# Domino_Pi.net
KiCad netlist of a schematic drawn in EAGLE
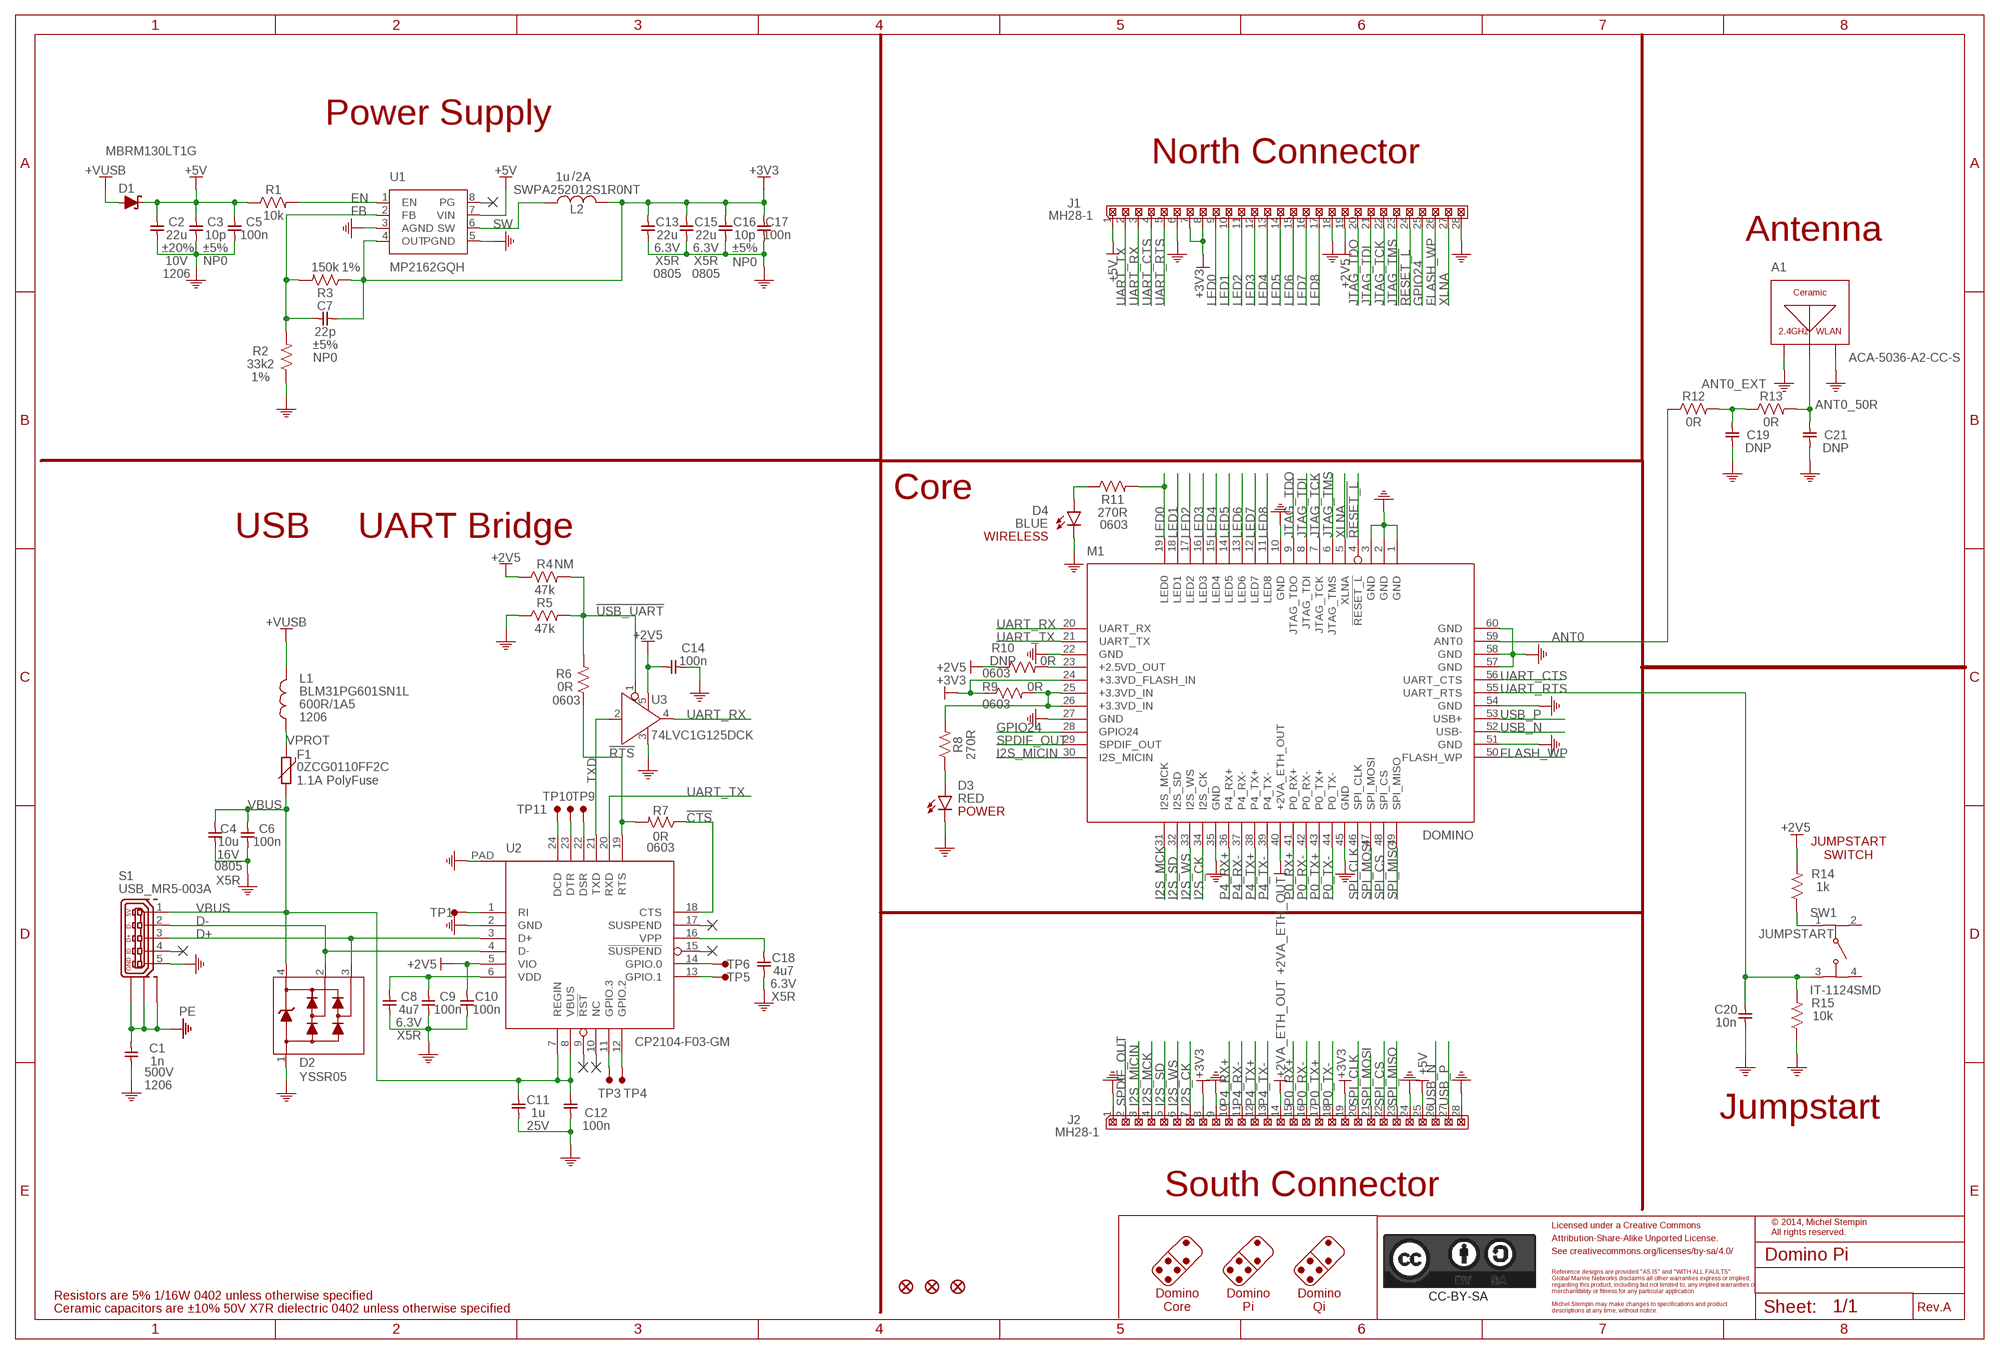
[diagram p0: schematic, sheet 1]

(export (version "E")
  (design (tool "Eeschema 10.0.6"))
  (components
    (comp (ref "A1")
      (value "ACA-5036-A2-CC-S")
      (footprint "eagle-import:ACA-5036-A2-CC-S")
      (libsource (lib "eagle-import") (part "ACA-5036-A2-CC-S"))
    )
    (comp (ref "C1")
      (value "1n")
      (footprint "eagle-import:C1206")
      (fields
        (field (name "SIZE") "1206")
        (field (name "PARTNO") "C1206_1n_X7R_10%_CER_500V")
        (field (name "VOLT") "500V")
      )
      (libsource (lib "eagle-import") (part "CAP_1206"))
    )
    (comp (ref "C2")
      (value "22u")
      (footprint "eagle-import:C1206")
      (fields
        (field (name "SIZE") "1206")
        (field (name "PARTNO") "C1206_22u_X7R_20%_CER_10V")
        (field (name "TOL") "±20%")
        (field (name "VOLT") "10V")
      )
      (libsource (lib "eagle-import") (part "CAP_1206"))
    )
    (comp (ref "C3")
      (value "10p")
      (footprint "eagle-import:C0402")
      (fields
        (field (name "PARTNO") "C0402_10p_NP0_5%_CER_50V")
        (field (name "TC") "NP0")
        (field (name "TOL") "±5%")
      )
      (libsource (lib "eagle-import") (part "CAP_0402"))
    )
    (comp (ref "C4")
      (value "10u")
      (footprint "eagle-import:C0805")
      (fields
        (field (name "SIZE") "0805")
        (field (name "PARTNO") "C0805_10u_X5R_10%_CER_16V")
        (field (name "TC") "X5R")
        (field (name "VOLT") "16V")
      )
      (libsource (lib "eagle-import") (part "CAP_0805"))
    )
    (comp (ref "C5")
      (value "100n")
      (footprint "eagle-import:C0402")
      (fields (field (name "PARTNO") "C0402_100n_X7R_10%_CER_50V"))
      (libsource (lib "eagle-import") (part "CAP_0402"))
    )
    (comp (ref "C6")
      (value "100n")
      (footprint "eagle-import:C0402")
      (fields (field (name "PARTNO") "C0402_100n_X7R_10%_CER_50V"))
      (libsource (lib "eagle-import") (part "CAP_0402"))
    )
    (comp (ref "C7")
      (value "22p")
      (footprint "eagle-import:C0402")
      (fields
        (field (name "PARTNO") "C0402_22p_NP0_5%_CER_50V")
        (field (name "TC") "NP0")
        (field (name "TOL") "±5%")
      )
      (libsource (lib "eagle-import") (part "CAP_0402"))
    )
    (comp (ref "C8")
      (value "4u7")
      (footprint "eagle-import:C0402")
      (fields
        (field (name "PARTNO") "C0402_4u7_X5R_10%_CER_6V3")
        (field (name "TC") "X5R")
        (field (name "VOLT") "6.3V")
      )
      (libsource (lib "eagle-import") (part "CAP_0402"))
    )
    (comp (ref "C9")
      (value "100n")
      (footprint "eagle-import:C0402")
      (fields (field (name "PARTNO") "C0402_100n_X7R_10%_CER_50V"))
      (libsource (lib "eagle-import") (part "CAP_0402"))
    )
    (comp (ref "C10")
      (value "100n")
      (footprint "eagle-import:C0402")
      (fields (field (name "PARTNO") "C0402_100n_X7R_10%_CER_50V"))
      (libsource (lib "eagle-import") (part "CAP_0402"))
    )
    (comp (ref "C11")
      (value "1u")
      (footprint "eagle-import:C0402")
      (fields (field (name "PARTNO") "C0402_1u_X7R_10%_CER_25V") (field (name "VOLT") "25V"))
      (libsource (lib "eagle-import") (part "CAP_0402"))
    )
    (comp (ref "C12")
      (value "100n")
      (footprint "eagle-import:C0402")
      (fields (field (name "PARTNO") "C0402_100n_X7R_10%_CER_50V"))
      (libsource (lib "eagle-import") (part "CAP_0402"))
    )
    (comp (ref "C13")
      (value "22u")
      (footprint "eagle-import:C0805")
      (fields
        (field (name "SIZE") "0805")
        (field (name "PARTNO") "C0805_22u_X5R_20%_CER_6V3")
        (field (name "TC") "X5R")
        (field (name "VOLT") "6.3V")
      )
      (libsource (lib "eagle-import") (part "CAP_0805"))
    )
    (comp (ref "C14")
      (value "100n")
      (footprint "eagle-import:C0402")
      (fields (field (name "PARTNO") "C0402_100n_X7R_10%_CER_50V"))
      (libsource (lib "eagle-import") (part "CAP_0402"))
    )
    (comp (ref "C15")
      (value "22u")
      (footprint "eagle-import:C0805")
      (fields
        (field (name "SIZE") "0805")
        (field (name "PARTNO") "C0805_22u_X5R_20%_CER_6V3")
        (field (name "TC") "X5R")
        (field (name "VOLT") "6.3V")
      )
      (libsource (lib "eagle-import") (part "CAP_0805"))
    )
    (comp (ref "C16")
      (value "10p")
      (footprint "eagle-import:C0402")
      (fields
        (field (name "PARTNO") "C0402_10p_NP0_5%_CER_50V")
        (field (name "TC") "NP0")
        (field (name "TOL") "±5%")
      )
      (libsource (lib "eagle-import") (part "CAP_0402"))
    )
    (comp (ref "C17")
      (value "100n")
      (footprint "eagle-import:C0402")
      (fields (field (name "PARTNO") "C0402_100n_X7R_10%_CER_50V"))
      (libsource (lib "eagle-import") (part "CAP_0402"))
    )
    (comp (ref "C18")
      (value "4u7")
      (footprint "eagle-import:C0402")
      (fields
        (field (name "PARTNO") "C0402_4u7_X5R_10%_CER_6V3")
        (field (name "TC") "X5R")
        (field (name "VOLT") "6.3V")
      )
      (libsource (lib "eagle-import") (part "CAP_0402"))
    )
    (comp (ref "C19")
      (value "DNP")
      (footprint "eagle-import:C0402")
      (fields (field (name "PARTNO") "C0402_DNP"))
      (libsource (lib "eagle-import") (part "CAP_0402"))
    )
    (comp (ref "C20")
      (value "10n")
      (footprint "eagle-import:C0402")
      (fields (field (name "PARTNO") "C0402_10n_X7R_10%_CER_50V"))
      (libsource (lib "eagle-import") (part "CAP_0402"))
    )
    (comp (ref "C21")
      (value "DNP")
      (footprint "eagle-import:C0402")
      (fields (field (name "PARTNO") "C0402_DNP"))
      (libsource (lib "eagle-import") (part "CAP_0402"))
    )
    (comp (ref "CC-BY-SA")
      (value "CC-BY-SA_LOGO")
      (footprint "eagle-import:CC-BY-SA_LOGO")
      (libsource (lib "eagle-import") (part "CC-BY-SA_LOGO"))
    )
    (comp (ref "D1")
      (value "MBRM130LT1G")
      (footprint "eagle-import:DO-216AA")
      (libsource (lib "eagle-import") (part "MBRM130LT1G"))
    )
    (comp (ref "D2")
      (value "YSSR05")
      (footprint "eagle-import:SOT143B")
      (libsource (lib "eagle-import") (part "YSSR05"))
    )
    (comp (ref "D3")
      (value "RED")
      (footprint "eagle-import:LED0603")
      (fields (field (name "PARTNO") "LED0603-RED"))
      (libsource (lib "eagle-import") (part "LED_0603"))
    )
    (comp (ref "D4")
      (value "BLUE")
      (footprint "eagle-import:LED0603")
      (fields (field (name "PARTNO") "LED0603-BLUE"))
      (libsource (lib "eagle-import") (part "LED_0603"))
    )
    (comp (ref "F1")
      (value "0ZCG0110FF2C")
      (footprint "eagle-import:PTC1812")
      (fields (field (name "RATE") "1.1A"))
      (libsource (lib "eagle-import") (part "0ZCG0110FF2C"))
    )
    (comp (ref "F2")
      (value "FIDUCIAL")
      (footprint "eagle-import:FIDUCIAL")
      (libsource (lib "eagle-import") (part "FIDUCIAL"))
    )
    (comp (ref "F3")
      (value "FIDUCIAL")
      (footprint "eagle-import:FIDUCIAL")
      (libsource (lib "eagle-import") (part "FIDUCIAL"))
    )
    (comp (ref "F4")
      (value "FIDUCIAL")
      (footprint "eagle-import:FIDUCIAL")
      (libsource (lib "eagle-import") (part "FIDUCIAL"))
    )
    (comp (ref "J1")
      (value "MH28-1")
      (footprint "eagle-import:MH28-1-0.1")
      (fields (field (name "PARTNO") "MH28-1-0.1"))
      (libsource (lib "eagle-import") (part "MH28-1"))
    )
    (comp (ref "J2")
      (value "MH28-1")
      (footprint "eagle-import:MH28-1-0.1")
      (fields (field (name "PARTNO") "MH28-1-0.1"))
      (libsource (lib "eagle-import") (part "MH28-1"))
    )
    (comp (ref "L1")
      (value "BLM31PG601SN1L")
      (footprint "eagle-import:FB1206")
      (fields (field (name "SIZE") "1206") (field (name "OPT") "600R/1A5"))
      (libsource (lib "eagle-import") (part "FB_1206"))
    )
    (comp (ref "L2")
      (value "SWPA252012S1R0NT")
      (footprint "eagle-import:SWPA252012S")
      (fields
        (field (name "INDUCTANCE") "1u")
        (field (name "RATE") "2A")
        (field (name "PARTNO") "SWPA252012SMT")
        (field (name "RATE_1") "2A")
      )
      (libsource (lib "eagle-import") (part "SWPA252012S?NT1R0"))
    )
    (comp (ref "M1")
      (value "DOMINO")
      (footprint "eagle-import:DOMINO")
      (fields (field (name "PARTNO") "DOMINO-CORE"))
      (libsource (lib "eagle-import") (part "DOMINO"))
    )
    (comp (ref "R1")
      (value "10k")
      (footprint "eagle-import:R0402")
      (fields (field (name "PARTNO") "R0402_10k_5%_62.5mW"))
      (libsource (lib "eagle-import") (part "RES_0402"))
    )
    (comp (ref "R2")
      (value "33k2")
      (footprint "eagle-import:R0402")
      (fields (field (name "PARTNO") "R0402_33k2_1%_62.5mW") (field (name "TOL") "1%"))
      (libsource (lib "eagle-import") (part "RES_0402"))
    )
    (comp (ref "R3")
      (value "150k")
      (footprint "eagle-import:R0402")
      (fields (field (name "PARTNO") "R0402_150k_1%_62.5mW") (field (name "TOL") "1%"))
      (libsource (lib "eagle-import") (part "RES_0402"))
    )
    (comp (ref "R4")
      (value "47k")
      (footprint "eagle-import:R0402")
      (fields (field (name "PARTNO") "R0402_47k_5%_62.5mW"))
      (libsource (lib "eagle-import") (part "RES_0402"))
    )
    (comp (ref "R5")
      (value "47k")
      (footprint "eagle-import:R0402")
      (fields (field (name "PARTNO") "R0402_47k_5%_62.5mW"))
      (libsource (lib "eagle-import") (part "RES_0402"))
    )
    (comp (ref "R6")
      (value "0R")
      (footprint "eagle-import:R0603")
      (fields (field (name "SIZE") "0603") (field (name "PARTNO") "R0603_0R_5%_125mW"))
      (libsource (lib "eagle-import") (part "RES_0603"))
    )
    (comp (ref "R7")
      (value "0R")
      (footprint "eagle-import:R0603")
      (fields (field (name "SIZE") "0603") (field (name "PARTNO") "R0603_0R_5%_125mW"))
      (libsource (lib "eagle-import") (part "RES_0603"))
    )
    (comp (ref "R8")
      (value "270R")
      (footprint "eagle-import:R0402")
      (fields (field (name "PARTNO") "R0402_270R_5%_62.5mW"))
      (libsource (lib "eagle-import") (part "RES_0402"))
    )
    (comp (ref "R9")
      (value "0R")
      (footprint "eagle-import:R0603")
      (fields (field (name "SIZE") "0603") (field (name "PARTNO") "R0603_0R_5%_125mW"))
      (libsource (lib "eagle-import") (part "RES_0603"))
    )
    (comp (ref "R10")
      (value "0R")
      (footprint "eagle-import:R0603")
      (fields (field (name "SIZE") "0603") (field (name "PARTNO") "R0603_0R_5%_125mW"))
      (libsource (lib "eagle-import") (part "RES_0603"))
    )
    (comp (ref "R11")
      (value "270R")
      (footprint "eagle-import:R0603")
      (fields (field (name "SIZE") "0603") (field (name "PARTNO") "R0603_270R_5%_125mW"))
      (libsource (lib "eagle-import") (part "RES_0603"))
    )
    (comp (ref "R12")
      (value "0R")
      (footprint "eagle-import:R0402")
      (fields (field (name "PARTNO") "R0402_0R_5%_62.5mW"))
      (libsource (lib "eagle-import") (part "RES_0402"))
    )
    (comp (ref "R13")
      (value "0R")
      (footprint "eagle-import:R0402")
      (fields (field (name "PARTNO") "R0402_0R_5%_62.5mW"))
      (libsource (lib "eagle-import") (part "RES_0402"))
    )
    (comp (ref "R14")
      (value "1k")
      (footprint "eagle-import:R0402")
      (fields (field (name "PARTNO") "R0402_1k_5%_62.5mW"))
      (libsource (lib "eagle-import") (part "RES_0402"))
    )
    (comp (ref "R15")
      (value "10k")
      (footprint "eagle-import:R0402")
      (fields (field (name "PARTNO") "R0402_10k_5%_62.5mW"))
      (libsource (lib "eagle-import") (part "RES_0402"))
    )
    (comp (ref "S1")
      (value "USB_MR5-003A")
      (footprint "eagle-import:USB_MR5-003A")
      (fields (field (name "PARTNO") "USB MR5-003A"))
      (libsource (lib "eagle-import") (part "USB_MR5-003A"))
    )
    (comp (ref "SW1")
      (value "IT-1124SMD")
      (footprint "eagle-import:IT-1124SMD")
      (libsource (lib "eagle-import") (part "IT-1124SMD"))
    )
    (comp (ref "TP1")
      (value "TEST_PAD")
      (footprint "eagle-import:TEST_PAD")
      (libsource (lib "eagle-import") (part "TEST_PAD"))
    )
    (comp (ref "TP3")
      (value "TEST_PAD")
      (footprint "eagle-import:TEST_PAD")
      (libsource (lib "eagle-import") (part "TEST_PAD"))
    )
    (comp (ref "TP4")
      (value "TEST_PAD")
      (footprint "eagle-import:TEST_PAD")
      (libsource (lib "eagle-import") (part "TEST_PAD"))
    )
    (comp (ref "TP5")
      (value "TEST_PAD")
      (footprint "eagle-import:TEST_PAD")
      (libsource (lib "eagle-import") (part "TEST_PAD"))
    )
    (comp (ref "TP6")
      (value "TEST_PAD")
      (footprint "eagle-import:TEST_PAD")
      (libsource (lib "eagle-import") (part "TEST_PAD"))
    )
    (comp (ref "TP9")
      (value "TEST_PAD")
      (footprint "eagle-import:TEST_PAD")
      (libsource (lib "eagle-import") (part "TEST_PAD"))
    )
    (comp (ref "TP10")
      (value "TEST_PAD")
      (footprint "eagle-import:TEST_PAD")
      (libsource (lib "eagle-import") (part "TEST_PAD"))
    )
    (comp (ref "TP11")
      (value "TEST_PAD")
      (footprint "eagle-import:TEST_PAD")
      (libsource (lib "eagle-import") (part "TEST_PAD"))
    )
    (comp (ref "U1")
      (value "MP2162GQH")
      (footprint "eagle-import:QFN-8_2X1.5")
      (libsource (lib "eagle-import") (part "MP2162GQH"))
    )
    (comp (ref "U2")
      (value "CP2104-F03-GM")
      (footprint "eagle-import:QFN-25_4X4")
      (libsource (lib "eagle-import") (part "CP2104-F03-GM"))
    )
    (comp (ref "U3")
      (value "74LVC1G125DCK")
      (footprint "eagle-import:SC70")
      (fields (field (name "PARTNO") "74LVC1G125DCK "))
      (libsource (lib "eagle-import") (part "741G125DCKLVC"))
    )
  )
  (nets
    (net (code "1") (name "+2V5") (class "Default")
      (node (ref "C10") (pin "1") (pinfunction "1_1") (pintype "passive"))
      (node (ref "C14") (pin "2") (pinfunction "2_2") (pintype "passive"))
      (node (ref "J1") (pin "19") (pinfunction "19_19") (pintype "passive"))
      (node (ref "R10") (pin "1") (pinfunction "1_1") (pintype "passive"))
      (node (ref "R14") (pin "2") (pinfunction "2_2") (pintype "passive"))
      (node (ref "R4") (pin "1") (pinfunction "1_1") (pintype "passive"))
      (node (ref "U2") (pin "5") (pinfunction "VIO_5") (pintype "power_in"))
      (node (ref "U3") (pin "5") (pinfunction "VCC_5") (pintype "power_in"))
    )
    (net (code "2") (name "+2VA_ETH_OUT") (class "Default")
      (node (ref "J2") (pin "14") (pinfunction "14_14") (pintype "passive"))
      (node (ref "M1") (pin "40") (pinfunction "+2VA_ETH_OUT_40") (pintype "power_in"))
    )
    (net (code "3") (name "+3V3") (class "Default")
      (node (ref "C13") (pin "1") (pinfunction "1_1") (pintype "passive"))
      (node (ref "C15") (pin "1") (pinfunction "1_1") (pintype "passive"))
      (node (ref "C16") (pin "1") (pinfunction "1_1") (pintype "passive"))
      (node (ref "C17") (pin "1") (pinfunction "1_1") (pintype "passive"))
      (node (ref "C7") (pin "2") (pinfunction "2_2") (pintype "passive"))
      (node (ref "J1") (pin "7") (pinfunction "7_7") (pintype "passive"))
      (node (ref "J1") (pin "8") (pinfunction "8_8") (pintype "passive"))
      (node (ref "J2") (pin "19") (pinfunction "19_19") (pintype "passive"))
      (node (ref "J2") (pin "8") (pinfunction "8_8") (pintype "passive"))
      (node (ref "L2") (pin "2") (pinfunction "2_2") (pintype "passive"))
      (node (ref "M1") (pin "24") (pinfunction "+3.3VD_FLASH_IN_24") (pintype "power_in"))
      (node (ref "R3") (pin "1") (pinfunction "1_1") (pintype "passive"))
      (node (ref "R9") (pin "1") (pinfunction "1_1") (pintype "passive"))
      (node (ref "U1") (pin "4") (pinfunction "OUT_4") (pintype "power_in"))
    )
    (net (code "4") (name "+5V") (class "Default")
      (node (ref "C2") (pin "1") (pinfunction "1_1") (pintype "passive"))
      (node (ref "C3") (pin "1") (pinfunction "1_1") (pintype "passive"))
      (node (ref "C5") (pin "1") (pinfunction "1_1") (pintype "passive"))
      (node (ref "D1") (pin "1") (pinfunction "C_1") (pintype "passive"))
      (node (ref "J1") (pin "1") (pinfunction "1_1") (pintype "passive"))
      (node (ref "J2") (pin "25") (pinfunction "25_25") (pintype "passive"))
      (node (ref "R1") (pin "1") (pinfunction "1_1") (pintype "passive"))
      (node (ref "U1") (pin "7") (pinfunction "VIN_7") (pintype "power_in"))
    )
    (net (code "5") (name "+VUSB") (class "Default")
      (node (ref "D1") (pin "2") (pinfunction "A_2") (pintype "passive"))
      (node (ref "L1") (pin "1") (pinfunction "1_1") (pintype "passive"))
    )
    (net (code "6") (name "/ANT0") (class "Default")
      (node (ref "M1") (pin "59") (pinfunction "ANT0_59") (pintype "passive"))
      (node (ref "R12") (pin "1") (pinfunction "1_1") (pintype "passive"))
    )
    (net (code "7") (name "/ANT0_50R") (class "Default")
      (node (ref "A1") (pin "FEED") (pinfunction "A_FEED") (pintype "passive"))
      (node (ref "C21") (pin "1") (pinfunction "1_1") (pintype "passive"))
      (node (ref "R13") (pin "2") (pinfunction "2_2") (pintype "passive"))
    )
    (net (code "8") (name "/ANT0_EXT") (class "Default")
      (node (ref "C19") (pin "1") (pinfunction "1_1") (pintype "passive"))
      (node (ref "R12") (pin "2") (pinfunction "2_2") (pintype "passive"))
      (node (ref "R13") (pin "1") (pinfunction "1_1") (pintype "passive"))
    )
    (net (code "9") (name "/D+") (class "Default")
      (node (ref "D2") (pin "3") (pinfunction "P$3_3") (pintype "passive"))
      (node (ref "S1") (pin "3") (pinfunction "3_3") (pintype "passive"))
      (node (ref "U2") (pin "3") (pinfunction "D+_3") (pintype "passive"))
    )
    (net (code "10") (name "/D-") (class "Default")
      (node (ref "D2") (pin "2") (pinfunction "P$2_2") (pintype "passive"))
      (node (ref "S1") (pin "2") (pinfunction "2_2") (pintype "passive"))
      (node (ref "U2") (pin "4") (pinfunction "D-_4") (pintype "passive"))
    )
    (net (code "11") (name "/EN") (class "Default")
      (node (ref "R1") (pin "2") (pinfunction "2_2") (pintype "passive"))
      (node (ref "U1") (pin "1") (pinfunction "EN_1") (pintype "input"))
    )
    (net (code "12") (name "/FB") (class "Default")
      (node (ref "C7") (pin "1") (pinfunction "1_1") (pintype "passive"))
      (node (ref "R2") (pin "2") (pinfunction "2_2") (pintype "passive"))
      (node (ref "R3") (pin "2") (pinfunction "2_2") (pintype "passive"))
      (node (ref "U1") (pin "2") (pinfunction "FB_2") (pintype "passive"))
    )
    (net (code "13") (name "/FLASH_WP") (class "Default")
      (node (ref "J1") (pin "26") (pinfunction "26_26") (pintype "passive"))
      (node (ref "M1") (pin "50") (pinfunction "FLASH_WP_50") (pintype "bidirectional"))
    )
    (net (code "14") (name "/GPIO24") (class "Default")
      (node (ref "J1") (pin "25") (pinfunction "25_25") (pintype "passive"))
      (node (ref "M1") (pin "28") (pinfunction "GPIO24_28") (pintype "bidirectional"))
    )
    (net (code "15") (name "/I2S_CK") (class "Default")
      (node (ref "J2") (pin "7") (pinfunction "7_7") (pintype "passive"))
      (node (ref "M1") (pin "34") (pinfunction "I2S_CK_34") (pintype "bidirectional"))
    )
    (net (code "16") (name "/I2S_MCK") (class "Default")
      (node (ref "J2") (pin "4") (pinfunction "4_4") (pintype "passive"))
      (node (ref "M1") (pin "31") (pinfunction "I2S_MCK_31") (pintype "bidirectional"))
    )
    (net (code "17") (name "/I2S_MICIN") (class "Default")
      (node (ref "J2") (pin "3") (pinfunction "3_3") (pintype "passive"))
      (node (ref "M1") (pin "30") (pinfunction "I2S_MICIN_30") (pintype "bidirectional"))
    )
    (net (code "18") (name "/I2S_SD") (class "Default")
      (node (ref "J2") (pin "5") (pinfunction "5_5") (pintype "passive"))
      (node (ref "M1") (pin "32") (pinfunction "I2S_SD_32") (pintype "bidirectional"))
    )
    (net (code "19") (name "/I2S_WS") (class "Default")
      (node (ref "J2") (pin "6") (pinfunction "6_6") (pintype "passive"))
      (node (ref "M1") (pin "33") (pinfunction "I2S_WS_33") (pintype "bidirectional"))
    )
    (net (code "20") (name "/JTAG_TCK") (class "Default")
      (node (ref "J1") (pin "22") (pinfunction "22_22") (pintype "passive"))
      (node (ref "M1") (pin "7") (pinfunction "JTAG_TCK_7") (pintype "bidirectional"))
    )
    (net (code "21") (name "/JTAG_TDI") (class "Default")
      (node (ref "J1") (pin "21") (pinfunction "21_21") (pintype "passive"))
      (node (ref "M1") (pin "8") (pinfunction "JTAG_TDI_8") (pintype "bidirectional"))
    )
    (net (code "22") (name "/JTAG_TDO") (class "Default")
      (node (ref "J1") (pin "20") (pinfunction "20_20") (pintype "passive"))
      (node (ref "M1") (pin "9") (pinfunction "JTAG_TDO_9") (pintype "bidirectional"))
    )
    (net (code "23") (name "/JTAG_TMS") (class "Default")
      (node (ref "J1") (pin "23") (pinfunction "23_23") (pintype "passive"))
      (node (ref "M1") (pin "6") (pinfunction "JTAG_TMS_6") (pintype "bidirectional"))
    )
    (net (code "24") (name "/JUMPSTART") (class "Default")
      (node (ref "R14") (pin "1") (pinfunction "1_1") (pintype "passive"))
      (node (ref "SW1") (pin "1") (pinfunction "1_1") (pintype "passive"))
    )
    (net (code "25") (name "/LED0") (class "Default")
      (node (ref "J1") (pin "9") (pinfunction "9_9") (pintype "passive"))
      (node (ref "M1") (pin "19") (pinfunction "LED0_19") (pintype "bidirectional"))
      (node (ref "R11") (pin "2") (pinfunction "2_2") (pintype "passive"))
    )
    (net (code "26") (name "/LED1") (class "Default")
      (node (ref "J1") (pin "10") (pinfunction "10_10") (pintype "passive"))
      (node (ref "M1") (pin "18") (pinfunction "LED1_18") (pintype "bidirectional"))
    )
    (net (code "27") (name "/LED2") (class "Default")
      (node (ref "J1") (pin "11") (pinfunction "11_11") (pintype "passive"))
      (node (ref "M1") (pin "17") (pinfunction "LED2_17") (pintype "bidirectional"))
    )
    (net (code "28") (name "/LED3") (class "Default")
      (node (ref "J1") (pin "12") (pinfunction "12_12") (pintype "passive"))
      (node (ref "M1") (pin "16") (pinfunction "LED3_16") (pintype "bidirectional"))
    )
    (net (code "29") (name "/LED4") (class "Default")
      (node (ref "J1") (pin "13") (pinfunction "13_13") (pintype "passive"))
      (node (ref "M1") (pin "15") (pinfunction "LED4_15") (pintype "bidirectional"))
    )
    (net (code "30") (name "/LED5") (class "Default")
      (node (ref "J1") (pin "14") (pinfunction "14_14") (pintype "passive"))
      (node (ref "M1") (pin "14") (pinfunction "LED5_14") (pintype "bidirectional"))
    )
    (net (code "31") (name "/LED6") (class "Default")
      (node (ref "J1") (pin "15") (pinfunction "15_15") (pintype "passive"))
      (node (ref "M1") (pin "13") (pinfunction "LED6_13") (pintype "bidirectional"))
    )
    (net (code "32") (name "/LED7") (class "Default")
      (node (ref "J1") (pin "16") (pinfunction "16_16") (pintype "passive"))
      (node (ref "M1") (pin "12") (pinfunction "LED7_12") (pintype "bidirectional"))
    )
    (net (code "33") (name "/LED8") (class "Default")
      (node (ref "J1") (pin "17") (pinfunction "17_17") (pintype "passive"))
      (node (ref "M1") (pin "11") (pinfunction "LED8_11") (pintype "bidirectional"))
    )
    (net (code "34") (name "/P0_RX+") (class "Default")
      (node (ref "J2") (pin "15") (pinfunction "15_15") (pintype "passive"))
      (node (ref "M1") (pin "41") (pinfunction "P0_RX+_41") (pintype "passive"))
    )
    (net (code "35") (name "/P0_RX-") (class "Default")
      (node (ref "J2") (pin "16") (pinfunction "16_16") (pintype "passive"))
      (node (ref "M1") (pin "42") (pinfunction "P0_RX-_42") (pintype "passive"))
    )
    (net (code "36") (name "/P0_TX+") (class "Default")
      (node (ref "J2") (pin "17") (pinfunction "17_17") (pintype "passive"))
      (node (ref "M1") (pin "43") (pinfunction "P0_TX+_43") (pintype "passive"))
    )
    (net (code "37") (name "/P0_TX-") (class "Default")
      (node (ref "J2") (pin "18") (pinfunction "18_18") (pintype "passive"))
      (node (ref "M1") (pin "44") (pinfunction "P0_TX-_44") (pintype "passive"))
    )
    (net (code "38") (name "/P4_RX+") (class "Default")
      (node (ref "J2") (pin "10") (pinfunction "10_10") (pintype "passive"))
      (node (ref "M1") (pin "36") (pinfunction "P4_RX+_36") (pintype "passive"))
    )
    (net (code "39") (name "/P4_RX-") (class "Default")
      (node (ref "J2") (pin "11") (pinfunction "11_11") (pintype "passive"))
      (node (ref "M1") (pin "37") (pinfunction "P4_RX-_37") (pintype "passive"))
    )
    (net (code "40") (name "/P4_TX+") (class "Default")
      (node (ref "J2") (pin "12") (pinfunction "12_12") (pintype "passive"))
      (node (ref "M1") (pin "38") (pinfunction "P4_TX+_38") (pintype "passive"))
    )
    (net (code "41") (name "/P4_TX-") (class "Default")
      (node (ref "J2") (pin "13") (pinfunction "13_13") (pintype "passive"))
      (node (ref "M1") (pin "39") (pinfunction "P4_TX-_39") (pintype "passive"))
    )
    (net (code "42") (name "/SPDIF_OUT") (class "Default")
      (node (ref "J2") (pin "2") (pinfunction "2_2") (pintype "passive"))
      (node (ref "M1") (pin "29") (pinfunction "SPDIF_OUT_29") (pintype "bidirectional"))
    )
    (net (code "43") (name "/SPI_CLK") (class "Default")
      (node (ref "J2") (pin "20") (pinfunction "20_20") (pintype "passive"))
      (node (ref "M1") (pin "46") (pinfunction "SPI_CLK_46") (pintype "bidirectional"))
    )
    (net (code "44") (name "/SPI_CS") (class "Default")
      (node (ref "J2") (pin "22") (pinfunction "22_22") (pintype "passive"))
      (node (ref "M1") (pin "48") (pinfunction "SPI_CS_48") (pintype "bidirectional"))
    )
    (net (code "45") (name "/SPI_MISO") (class "Default")
      (node (ref "J2") (pin "23") (pinfunction "23_23") (pintype "passive"))
      (node (ref "M1") (pin "49") (pinfunction "SPI_MISO_49") (pintype "bidirectional"))
    )
    (net (code "46") (name "/SPI_MOSI") (class "Default")
      (node (ref "J2") (pin "21") (pinfunction "21_21") (pintype "passive"))
      (node (ref "M1") (pin "47") (pinfunction "SPI_MOSI_47") (pintype "bidirectional"))
    )
    (net (code "47") (name "/SW") (class "Default")
      (node (ref "L2") (pin "1") (pinfunction "1_1") (pintype "passive"))
      (node (ref "U1") (pin "6") (pinfunction "SW_6") (pintype "passive"))
    )
    (net (code "48") (name "/TXD") (class "Default")
      (node (ref "U2") (pin "21") (pinfunction "TXD_21") (pintype "output"))
      (node (ref "U3") (pin "2") (pinfunction "A_2") (pintype "input"))
    )
    (net (code "49") (name "/UART_CTS") (class "Default")
      (node (ref "J1") (pin "4") (pinfunction "4_4") (pintype "passive"))
      (node (ref "M1") (pin "56") (pinfunction "UART_CTS_56") (pintype "bidirectional"))
    )
    (net (code "50") (name "/UART_RTS") (class "Default")
      (node (ref "C20") (pin "1") (pinfunction "1_1") (pintype "passive"))
      (node (ref "J1") (pin "5") (pinfunction "5_5") (pintype "passive"))
      (node (ref "M1") (pin "55") (pinfunction "UART_RTS_55") (pintype "bidirectional"))
      (node (ref "R15") (pin "2") (pinfunction "2_2") (pintype "passive"))
      (node (ref "SW1") (pin "3") (pinfunction "3_3") (pintype "passive"))
    )
    (net (code "51") (name "/UART_RX") (class "Default")
      (node (ref "J1") (pin "3") (pinfunction "3_3") (pintype "passive"))
      (node (ref "M1") (pin "20") (pinfunction "UART_RX_20") (pintype "bidirectional"))
      (node (ref "U3") (pin "4") (pinfunction "Y_4") (pintype "tri_state"))
    )
    (net (code "52") (name "/UART_TX") (class "Default")
      (node (ref "J1") (pin "2") (pinfunction "2_2") (pintype "passive"))
      (node (ref "M1") (pin "21") (pinfunction "UART_TX_21") (pintype "bidirectional"))
      (node (ref "U2") (pin "20") (pinfunction "RXD_20") (pintype "input"))
    )
    (net (code "53") (name "/USB_N") (class "Default")
      (node (ref "J2") (pin "26") (pinfunction "26_26") (pintype "passive"))
      (node (ref "M1") (pin "52") (pinfunction "USB-_52") (pintype "passive"))
    )
    (net (code "54") (name "/USB_P") (class "Default")
      (node (ref "J2") (pin "27") (pinfunction "27_27") (pintype "passive"))
      (node (ref "M1") (pin "53") (pinfunction "USB+_53") (pintype "passive"))
    )
    (net (code "55") (name "/VBUS") (class "Default")
      (node (ref "C11") (pin "1") (pinfunction "1_1") (pintype "passive"))
      (node (ref "C12") (pin "1") (pinfunction "1_1") (pintype "passive"))
      (node (ref "C4") (pin "1") (pinfunction "1_1") (pintype "passive"))
      (node (ref "C6") (pin "1") (pinfunction "1_1") (pintype "passive"))
      (node (ref "D2") (pin "4") (pinfunction "P$4_4") (pintype "passive"))
      (node (ref "F1") (pin "2") (pinfunction "2_2") (pintype "passive"))
      (node (ref "S1") (pin "1") (pinfunction "1_1") (pintype "passive"))
      (node (ref "U2") (pin "7") (pinfunction "REGIN_7") (pintype "power_in"))
      (node (ref "U2") (pin "8") (pinfunction "VBUS_8") (pintype "input"))
    )
    (net (code "56") (name "/VPROT") (class "Default")
      (node (ref "F1") (pin "1") (pinfunction "1_1") (pintype "passive"))
      (node (ref "L1") (pin "2") (pinfunction "2_2") (pintype "passive"))
    )
    (net (code "57") (name "/XLNA") (class "Default")
      (node (ref "J1") (pin "27") (pinfunction "27_27") (pintype "passive"))
      (node (ref "M1") (pin "5") (pinfunction "XLNA_5") (pintype "bidirectional"))
    )
    (net (code "58") (name "/~{CTS}") (class "Default")
      (node (ref "R7") (pin "1") (pinfunction "1_1") (pintype "passive"))
      (node (ref "U2") (pin "18") (pinfunction "CTS_18") (pintype "input"))
    )
    (net (code "59") (name "/~{RESET_L}") (class "Default")
      (node (ref "J1") (pin "24") (pinfunction "24_24") (pintype "passive"))
      (node (ref "M1") (pin "4") (pinfunction "~{RESET_L}_4") (pintype "input"))
    )
    (net (code "60") (name "/~{RTS}") (class "Default")
      (node (ref "R6") (pin "1") (pinfunction "1_1") (pintype "passive"))
      (node (ref "R7") (pin "2") (pinfunction "2_2") (pintype "passive"))
      (node (ref "U2") (pin "19") (pinfunction "RTS_19") (pintype "output"))
    )
    (net (code "61") (name "/~{USB_UART}") (class "Default")
      (node (ref "R4") (pin "2") (pinfunction "2_2") (pintype "passive"))
      (node (ref "R5") (pin "2") (pinfunction "2_2") (pintype "passive"))
      (node (ref "R6") (pin "2") (pinfunction "2_2") (pintype "passive"))
      (node (ref "U3") (pin "1") (pinfunction "~{OE}_1") (pintype "input"))
    )
    (net (code "62") (name "GND") (class "Default")
      (node (ref "A1") (pin "GND$1") (pinfunction "GND_GND$1") (pintype "power_in"))
      (node (ref "A1") (pin "GND$2") (pinfunction "GND_GND$2") (pintype "power_in"))
      (node (ref "C1") (pin "2") (pinfunction "2_2") (pintype "passive"))
      (node (ref "C10") (pin "2") (pinfunction "2_2") (pintype "passive"))
      (node (ref "C11") (pin "2") (pinfunction "2_2") (pintype "passive"))
      (node (ref "C12") (pin "2") (pinfunction "2_2") (pintype "passive"))
      (node (ref "C13") (pin "2") (pinfunction "2_2") (pintype "passive"))
      (node (ref "C14") (pin "1") (pinfunction "1_1") (pintype "passive"))
      (node (ref "C15") (pin "2") (pinfunction "2_2") (pintype "passive"))
      (node (ref "C16") (pin "2") (pinfunction "2_2") (pintype "passive"))
      (node (ref "C17") (pin "2") (pinfunction "2_2") (pintype "passive"))
      (node (ref "C18") (pin "2") (pinfunction "2_2") (pintype "passive"))
      (node (ref "C19") (pin "2") (pinfunction "2_2") (pintype "passive"))
      (node (ref "C2") (pin "2") (pinfunction "2_2") (pintype "passive"))
      (node (ref "C20") (pin "2") (pinfunction "2_2") (pintype "passive"))
      (node (ref "C21") (pin "2") (pinfunction "2_2") (pintype "passive"))
      (node (ref "C3") (pin "2") (pinfunction "2_2") (pintype "passive"))
      (node (ref "C4") (pin "2") (pinfunction "2_2") (pintype "passive"))
      (node (ref "C5") (pin "2") (pinfunction "2_2") (pintype "passive"))
      (node (ref "C6") (pin "2") (pinfunction "2_2") (pintype "passive"))
      (node (ref "C8") (pin "2") (pinfunction "2_2") (pintype "passive"))
      (node (ref "C9") (pin "2") (pinfunction "2_2") (pintype "passive"))
      (node (ref "D2") (pin "1") (pinfunction "P$1_1") (pintype "passive"))
      (node (ref "D3") (pin "1") (pinfunction "C_1") (pintype "passive"))
      (node (ref "D4") (pin "1") (pinfunction "C_1") (pintype "passive"))
      (node (ref "J1") (pin "18") (pinfunction "18_18") (pintype "passive"))
      (node (ref "J1") (pin "28") (pinfunction "28_28") (pintype "passive"))
      (node (ref "J1") (pin "6") (pinfunction "6_6") (pintype "passive"))
      (node (ref "J2") (pin "1") (pinfunction "1_1") (pintype "passive"))
      (node (ref "J2") (pin "24") (pinfunction "24_24") (pintype "passive"))
      (node (ref "J2") (pin "28") (pinfunction "28_28") (pintype "passive"))
      (node (ref "J2") (pin "9") (pinfunction "9_9") (pintype "passive"))
      (node (ref "M1") (pin "1") (pinfunction "GND_1") (pintype "power_in"))
      (node (ref "M1") (pin "10") (pinfunction "GND_10") (pintype "power_in"))
      (node (ref "M1") (pin "2") (pinfunction "GND_2") (pintype "power_in"))
      (node (ref "M1") (pin "22") (pinfunction "GND_22") (pintype "power_in"))
      (node (ref "M1") (pin "27") (pinfunction "GND_27") (pintype "power_in"))
      (node (ref "M1") (pin "3") (pinfunction "GND_3") (pintype "power_in"))
      (node (ref "M1") (pin "35") (pinfunction "GND_35") (pintype "power_in"))
      (node (ref "M1") (pin "45") (pinfunction "GND_45") (pintype "power_in"))
      (node (ref "M1") (pin "51") (pinfunction "GND_51") (pintype "power_in"))
      (node (ref "M1") (pin "54") (pinfunction "GND_54") (pintype "power_in"))
      (node (ref "M1") (pin "57") (pinfunction "GND_57") (pintype "power_in"))
      (node (ref "M1") (pin "58") (pinfunction "GND_58") (pintype "power_in"))
      (node (ref "M1") (pin "60") (pinfunction "GND_60") (pintype "power_in"))
      (node (ref "R15") (pin "1") (pinfunction "1_1") (pintype "passive"))
      (node (ref "R2") (pin "1") (pinfunction "1_1") (pintype "passive"))
      (node (ref "R5") (pin "1") (pinfunction "1_1") (pintype "passive"))
      (node (ref "S1") (pin "5") (pinfunction "5_5") (pintype "passive"))
      (node (ref "U1") (pin "3") (pinfunction "AGND_3") (pintype "power_in"))
      (node (ref "U1") (pin "5") (pinfunction "PGND_5") (pintype "power_in"))
      (node (ref "U2") (pin "2") (pinfunction "GND_2") (pintype "power_in"))
      (node (ref "U2") (pin "PAD") (pinfunction "PAD_PAD") (pintype "power_in"))
      (node (ref "U3") (pin "3") (pinfunction "GND_3") (pintype "power_in"))
    )
    (net (code "63") (name "Net-(D3-A)") (class "Default")
      (node (ref "D3") (pin "2") (pinfunction "A_2") (pintype "passive"))
      (node (ref "R8") (pin "1") (pinfunction "1_1") (pintype "passive"))
    )
    (net (code "64") (name "Net-(D4-A)") (class "Default")
      (node (ref "D4") (pin "2") (pinfunction "A_2") (pintype "passive"))
      (node (ref "R11") (pin "1") (pinfunction "1_1") (pintype "passive"))
    )
    (net (code "65") (name "Net-(M1-+2.5VD_OUT)") (class "Default")
      (node (ref "M1") (pin "23") (pinfunction "+2.5VD_OUT_23") (pintype "power_in"))
      (node (ref "R10") (pin "2") (pinfunction "2_2") (pintype "passive"))
    )
    (net (code "66") (name "Net-(M1-+3.3VD_IN-Pad25)") (class "Default")
      (node (ref "M1") (pin "25") (pinfunction "+3.3VD_IN_25") (pintype "power_in"))
      (node (ref "M1") (pin "26") (pinfunction "+3.3VD_IN_26") (pintype "power_in"))
      (node (ref "R8") (pin "2") (pinfunction "2_2") (pintype "passive"))
      (node (ref "R9") (pin "2") (pinfunction "2_2") (pintype "passive"))
    )
    (net (code "67") (name "Net-(TP1-PP)") (class "Default")
      (node (ref "TP1") (pin "1") (pinfunction "PP_1") (pintype "passive"))
      (node (ref "U2") (pin "1") (pinfunction "RI_1") (pintype "input"))
    )
    (net (code "68") (name "Net-(TP3-PP)") (class "Default")
      (node (ref "TP3") (pin "1") (pinfunction "PP_1") (pintype "passive"))
      (node (ref "U2") (pin "11") (pinfunction "GPIO.3_11") (pintype "bidirectional"))
    )
    (net (code "69") (name "Net-(TP4-PP)") (class "Default")
      (node (ref "TP4") (pin "1") (pinfunction "PP_1") (pintype "passive"))
      (node (ref "U2") (pin "12") (pinfunction "GPIO.2_12") (pintype "bidirectional"))
    )
    (net (code "70") (name "Net-(TP5-PP)") (class "Default")
      (node (ref "TP5") (pin "1") (pinfunction "PP_1") (pintype "passive"))
      (node (ref "U2") (pin "13") (pinfunction "GPIO.1_13") (pintype "bidirectional"))
    )
    (net (code "71") (name "Net-(TP6-PP)") (class "Default")
      (node (ref "TP6") (pin "1") (pinfunction "PP_1") (pintype "passive"))
      (node (ref "U2") (pin "14") (pinfunction "GPIO.0_14") (pintype "bidirectional"))
    )
    (net (code "72") (name "Net-(TP9-PP)") (class "Default")
      (node (ref "TP9") (pin "1") (pinfunction "PP_1") (pintype "passive"))
      (node (ref "U2") (pin "22") (pinfunction "DSR_22") (pintype "input"))
    )
    (net (code "73") (name "Net-(TP10-PP)") (class "Default")
      (node (ref "TP10") (pin "1") (pinfunction "PP_1") (pintype "passive"))
      (node (ref "U2") (pin "23") (pinfunction "DTR_23") (pintype "output"))
    )
    (net (code "74") (name "Net-(TP11-PP)") (class "Default")
      (node (ref "TP11") (pin "1") (pinfunction "PP_1") (pintype "passive"))
      (node (ref "U2") (pin "24") (pinfunction "DCD_24") (pintype "input"))
    )
    (net (code "75") (name "Net-(U2-VDD)") (class "Default")
      (node (ref "C8") (pin "1") (pinfunction "1_1") (pintype "passive"))
      (node (ref "C9") (pin "1") (pinfunction "1_1") (pintype "passive"))
      (node (ref "U2") (pin "6") (pinfunction "VDD_6") (pintype "power_in"))
    )
    (net (code "76") (name "Net-(U2-VPP)") (class "Default")
      (node (ref "C18") (pin "1") (pinfunction "1_1") (pintype "passive"))
      (node (ref "U2") (pin "16") (pinfunction "VPP_16") (pintype "passive"))
    )
    (net (code "77") (name "PE") (class "Default")
      (node (ref "C1") (pin "1") (pinfunction "1_1") (pintype "passive"))
      (node (ref "S1") (pin "S$1") (pinfunction "M0_S$1") (pintype "passive"))
      (node (ref "S1") (pin "S$2") (pinfunction "M1_S$2") (pintype "passive"))
      (node (ref "S1") (pin "S$3") (pinfunction "M2_S$3") (pintype "passive"))
    )
    (net (code "78") (name "unconnected-(S1-Pad4)") (class "Default")
      (node (ref "S1") (pin "4") (pinfunction "4_4") (pintype "passive"))
    )
    (net (code "79") (name "unconnected-(SW1-Pad2)") (class "Default")
      (node (ref "SW1") (pin "2") (pinfunction "2_2") (pintype "passive"))
    )
    (net (code "80") (name "unconnected-(SW1-Pad4)") (class "Default")
      (node (ref "SW1") (pin "4") (pinfunction "4_4") (pintype "passive"))
    )
    (net (code "81") (name "unconnected-(U1-PG-Pad8)") (class "Default")
      (node (ref "U1") (pin "8") (pinfunction "PG_8") (pintype "open_collector"))
    )
    (net (code "82") (name "unconnected-(U2-NC-Pad10)") (class "Default")
      (node (ref "U2") (pin "10") (pinfunction "NC_10") (pintype "no_connect"))
    )
    (net (code "83") (name "unconnected-(U2-SUSPEND-Pad17)") (class "Default")
      (node (ref "U2") (pin "17") (pinfunction "SUSPEND_17") (pintype "output"))
    )
    (net (code "84") (name "unconnected-(U2-~{RST}-Pad9)") (class "Default")
      (node (ref "U2") (pin "9") (pinfunction "~{RST}_9") (pintype "bidirectional"))
    )
    (net (code "85") (name "unconnected-(U2-~{SUSPEND}-Pad15)") (class "Default")
      (node (ref "U2") (pin "15") (pinfunction "~{SUSPEND}_15") (pintype "output"))
    )
  )
)
